# PIC32MXBOARD.net
KiCad netlist of a schematic drawn in EAGLE
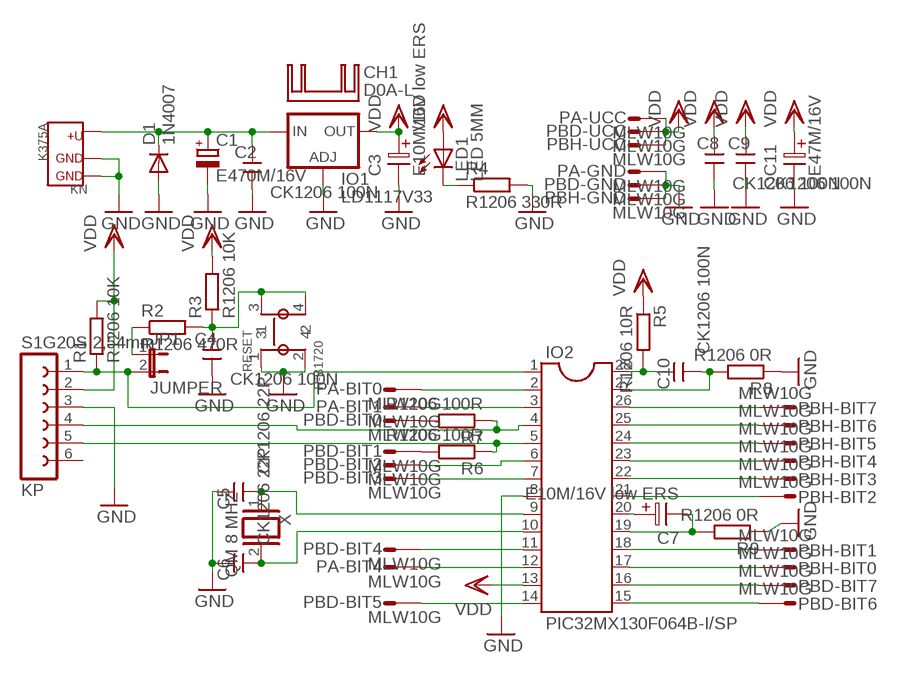
[diagram p0: schematic, sheet 1]

(export (version "E")
  (design (tool "Eeschema 10.0.6"))
  (components
    (comp (ref "C1")
      (value "E470M/16V")
      (footprint "eagle-import:E5-10,5")
      (libsource (lib "eagle-import") (part "CPOL-EUE5-10.5"))
    )
    (comp (ref "C2")
      (value "CK1206 100N")
      (footprint "eagle-import:CK+")
      (libsource (lib "eagle-import") (part "CK+"))
    )
    (comp (ref "C3")
      (value "E10M/16V low ERS")
      (footprint "eagle-import:ES-2,5L")
      (libsource (lib "eagle-import") (part "CEL2,5"))
    )
    (comp (ref "C4")
      (value "CK1206 100N")
      (footprint "eagle-import:CK+")
      (libsource (lib "eagle-import") (part "CK+"))
    )
    (comp (ref "C5")
      (value "CK1206 22P")
      (footprint "eagle-import:CK+")
      (libsource (lib "eagle-import") (part "CK+"))
    )
    (comp (ref "C6")
      (value "CK1206 22P")
      (footprint "eagle-import:CK+")
      (libsource (lib "eagle-import") (part "CK+"))
    )
    (comp (ref "C7")
      (value "E10M/16V low ERS")
      (footprint "eagle-import:ES-2,5L")
      (libsource (lib "eagle-import") (part "CEL2,5"))
    )
    (comp (ref "C8")
      (value "CK1206 100N")
      (footprint "eagle-import:CK+")
      (libsource (lib "eagle-import") (part "CK+"))
    )
    (comp (ref "C9")
      (value "CK1206 100N")
      (footprint "eagle-import:CK+")
      (libsource (lib "eagle-import") (part "CK+"))
    )
    (comp (ref "C10")
      (value "CK1206 100N")
      (footprint "eagle-import:CK+")
      (libsource (lib "eagle-import") (part "CK+"))
    )
    (comp (ref "C11")
      (value "E47M/16V")
      (footprint "eagle-import:ES-2,5L")
      (libsource (lib "eagle-import") (part "CEL2,5"))
    )
    (comp (ref "CH1")
      (value "D0A-L")
      (footprint "eagle-import:D02A-L")
      (libsource (lib "eagle-import") (part "D0A-L"))
    )
    (comp (ref "D1")
      (value "1N4007")
      (footprint "eagle-import:DO41-10")
      (libsource (lib "eagle-import") (part "1N4004"))
    )
    (comp (ref "IO1")
      (value "LD1117V33")
      (footprint "eagle-import:TO220L1")
      (libsource (lib "eagle-import") (part "LD117A?V33"))
    )
    (comp (ref "IO2")
      (value "PIC32MX130F064B-I/SP")
      (footprint "eagle-import:DIL28-3")
      (libsource (lib "eagle-import") (part "DIL28-3"))
    )
    (comp (ref "JP1")
      (value "JUMPER")
      (footprint "eagle-import:JP1")
      (libsource (lib "eagle-import") (part "JP1E"))
    )
    (comp (ref "KN")
      (value "K375A")
      (footprint "eagle-import:K375A")
      (libsource (lib "eagle-import") (part "K375A"))
    )
    (comp (ref "KP")
      (value "S1G20S 2,54mm")
      (footprint "eagle-import:FE06")
      (libsource (lib "eagle-import") (part "FE06-1"))
    )
    (comp (ref "LED1")
      (value "LED 5MM")
      (footprint "eagle-import:LED5MM")
      (libsource (lib "eagle-import") (part "LED5MM"))
    )
    (comp (ref "PA")
      (value "MLW10G")
      (footprint "eagle-import:MLW10G")
      (libsource (lib "eagle-import") (part "PSL10MLW10G"))
    )
    (comp (ref "PBD")
      (value "MLW10G")
      (footprint "eagle-import:MLW10G")
      (libsource (lib "eagle-import") (part "PSL10MLW10G"))
    )
    (comp (ref "PBH")
      (value "MLW10G")
      (footprint "eagle-import:MLW10G")
      (libsource (lib "eagle-import") (part "PSL10MLW10G"))
    )
    (comp (ref "R1")
      (value "R1206 10K")
      (footprint "eagle-import:R1206")
      (libsource (lib "eagle-import") (part "R-EU_R1206"))
    )
    (comp (ref "R2")
      (value "R1206 470R")
      (footprint "eagle-import:R1206")
      (libsource (lib "eagle-import") (part "R-EU_R1206"))
    )
    (comp (ref "R3")
      (value "R1206 10K")
      (footprint "eagle-import:R1206")
      (libsource (lib "eagle-import") (part "R-EU_R1206"))
    )
    (comp (ref "R4")
      (value "R1206 330R")
      (footprint "eagle-import:R1206")
      (libsource (lib "eagle-import") (part "R-EU_R1206"))
    )
    (comp (ref "R5")
      (value "R1206 10R")
      (footprint "eagle-import:R1206")
      (libsource (lib "eagle-import") (part "R-EU_R1206"))
    )
    (comp (ref "R6")
      (value "R1206 100R")
      (footprint "eagle-import:R1206")
      (libsource (lib "eagle-import") (part "R-EU_R1206"))
    )
    (comp (ref "R7")
      (value "R1206 100R")
      (footprint "eagle-import:R1206")
      (libsource (lib "eagle-import") (part "R-EU_R1206"))
    )
    (comp (ref "R8")
      (value "R1206 0R")
      (footprint "eagle-import:R1206")
      (libsource (lib "eagle-import") (part "R-EU_R1206"))
    )
    (comp (ref "R9")
      (value "R1206 0R")
      (footprint "eagle-import:R1206")
      (libsource (lib "eagle-import") (part "R-EU_R1206"))
    )
    (comp (ref "RESET")
      (value "P-B1720")
      (footprint "eagle-import:P-B1720")
      (libsource (lib "eagle-import") (part "P-B1720"))
    )
    (comp (ref "U$2")
      (value "RAM")
      (footprint "eagle-import:RAM")
      (libsource (lib "eagle-import") (part "RAM"))
    )
    (comp (ref "X")
      (value "QM 8 MHZ")
      (footprint "eagle-import:QS")
      (libsource (lib "eagle-import") (part "XTAL/S"))
    )
  )
  (nets
    (net (code "1") (name "GND") (class "Default")
      (node (ref "C1") (pin "-") (pinfunction "-_-") (pintype "passive"))
      (node (ref "C11") (pin "2") (pinfunction "2_2") (pintype "passive"))
      (node (ref "C2") (pin "2") (pinfunction "2_2") (pintype "passive"))
      (node (ref "C3") (pin "2") (pinfunction "2_2") (pintype "passive"))
      (node (ref "C4") (pin "2") (pinfunction "2_2") (pintype "passive"))
      (node (ref "C5") (pin "1") (pinfunction "1_1") (pintype "passive"))
      (node (ref "C6") (pin "1") (pinfunction "1_1") (pintype "passive"))
      (node (ref "C8") (pin "2") (pinfunction "2_2") (pintype "passive"))
      (node (ref "C9") (pin "2") (pinfunction "2_2") (pintype "passive"))
      (node (ref "D1") (pin "A") (pinfunction "A_A") (pintype "passive"))
      (node (ref "IO1") (pin "1") (pinfunction "ADJ_1") (pintype "input"))
      (node (ref "IO2") (pin "8") (pinfunction "8_8") (pintype "passive"))
      (node (ref "KN") (pin "1") (pinfunction "1_1") (pintype "bidirectional"))
      (node (ref "KN") (pin "3") (pinfunction "3_3") (pintype "bidirectional"))
      (node (ref "KP") (pin "3") (pinfunction "3_3") (pintype "passive"))
      (node (ref "PA") (pin "10") (pinfunction "S_10") (pintype "passive"))
      (node (ref "PBD") (pin "10") (pinfunction "S_10") (pintype "passive"))
      (node (ref "PBH") (pin "10") (pinfunction "S_10") (pintype "passive"))
      (node (ref "R4") (pin "2") (pinfunction "2_2") (pintype "passive"))
      (node (ref "R8") (pin "1") (pinfunction "1_1") (pintype "passive"))
      (node (ref "R9") (pin "1") (pinfunction "1_1") (pintype "passive"))
      (node (ref "RESET") (pin "1") (pinfunction "1_1") (pintype "bidirectional"))
      (node (ref "RESET") (pin "2") (pinfunction "2_2") (pintype "bidirectional"))
    )
    (net (code "2") (name "Net-(C4-Pad1)") (class "Default")
      (node (ref "C4") (pin "1") (pinfunction "1_1") (pintype "passive"))
      (node (ref "R2") (pin "2") (pinfunction "2_2") (pintype "passive"))
      (node (ref "R3") (pin "1") (pinfunction "1_1") (pintype "passive"))
      (node (ref "RESET") (pin "3") (pinfunction "3_3") (pintype "bidirectional"))
      (node (ref "RESET") (pin "4") (pinfunction "4_4") (pintype "bidirectional"))
    )
    (net (code "3") (name "Net-(C5-Pad2)") (class "Default")
      (node (ref "C5") (pin "2") (pinfunction "2_2") (pintype "passive"))
      (node (ref "IO2") (pin "9") (pinfunction "9_9") (pintype "passive"))
      (node (ref "X") (pin "1") (pinfunction "1_1") (pintype "passive"))
    )
    (net (code "4") (name "Net-(C6-Pad2)") (class "Default")
      (node (ref "C6") (pin "2") (pinfunction "2_2") (pintype "passive"))
      (node (ref "IO2") (pin "10") (pinfunction "10_10") (pintype "passive"))
      (node (ref "X") (pin "2") (pinfunction "2_2") (pintype "passive"))
    )
    (net (code "5") (name "Net-(C7-Pad1)") (class "Default")
      (node (ref "C7") (pin "1") (pinfunction "1_1") (pintype "passive"))
      (node (ref "IO2") (pin "20") (pinfunction "20_20") (pintype "passive"))
    )
    (net (code "6") (name "Net-(C7-Pad2)") (class "Default")
      (node (ref "C7") (pin "2") (pinfunction "2_2") (pintype "passive"))
      (node (ref "IO2") (pin "19") (pinfunction "19_19") (pintype "passive"))
      (node (ref "R9") (pin "2") (pinfunction "2_2") (pintype "passive"))
    )
    (net (code "7") (name "Net-(C10-Pad1)") (class "Default")
      (node (ref "C10") (pin "1") (pinfunction "1_1") (pintype "passive"))
      (node (ref "IO2") (pin "28") (pinfunction "28_28") (pintype "passive"))
      (node (ref "R5") (pin "2") (pinfunction "2_2") (pintype "passive"))
    )
    (net (code "8") (name "Net-(C10-Pad2)") (class "Default")
      (node (ref "C10") (pin "2") (pinfunction "2_2") (pintype "passive"))
      (node (ref "IO2") (pin "27") (pinfunction "27_27") (pintype "passive"))
      (node (ref "R8") (pin "2") (pinfunction "2_2") (pintype "passive"))
    )
    (net (code "9") (name "Net-(IO1-IN)") (class "Default")
      (node (ref "C1") (pin "+") (pinfunction "+_+") (pintype "passive"))
      (node (ref "C2") (pin "1") (pinfunction "1_1") (pintype "passive"))
      (node (ref "D1") (pin "C") (pinfunction "C_C") (pintype "passive"))
      (node (ref "IO1") (pin "3") (pinfunction "IN_3") (pintype "input"))
      (node (ref "KN") (pin "2") (pinfunction "2_2") (pintype "bidirectional"))
    )
    (net (code "10") (name "Net-(IO2-Pad1)") (class "Default")
      (node (ref "IO2") (pin "1") (pinfunction "1_1") (pintype "passive"))
      (node (ref "JP1") (pin "2") (pinfunction "2_2") (pintype "passive"))
      (node (ref "KP") (pin "1") (pinfunction "1_1") (pintype "passive"))
      (node (ref "R1") (pin "1") (pinfunction "1_1") (pintype "passive"))
    )
    (net (code "11") (name "Net-(IO2-Pad4)") (class "Default")
      (node (ref "IO2") (pin "4") (pinfunction "4_4") (pintype "passive"))
      (node (ref "KP") (pin "4") (pinfunction "4_4") (pintype "passive"))
      (node (ref "R7") (pin "1") (pinfunction "1_1") (pintype "passive"))
    )
    (net (code "12") (name "Net-(IO2-Pad5)") (class "Default")
      (node (ref "IO2") (pin "5") (pinfunction "5_5") (pintype "passive"))
      (node (ref "KP") (pin "5") (pinfunction "5_5") (pintype "passive"))
      (node (ref "R6") (pin "1") (pinfunction "1_1") (pintype "passive"))
    )
    (net (code "13") (name "Net-(JP1-Pad1)") (class "Default")
      (node (ref "JP1") (pin "1") (pinfunction "1_1") (pintype "passive"))
      (node (ref "R2") (pin "1") (pinfunction "1_1") (pintype "passive"))
    )
    (net (code "14") (name "Net-(LED1-C)") (class "Default")
      (node (ref "LED1") (pin "K") (pinfunction "C_K") (pintype "passive"))
      (node (ref "R4") (pin "1") (pinfunction "1_1") (pintype "passive"))
    )
    (net (code "15") (name "Net-(PAA-S)") (class "Default")
      (node (ref "IO2") (pin "2") (pinfunction "2_2") (pintype "passive"))
      (node (ref "PA") (pin "9") (pinfunction "S_9") (pintype "passive"))
    )
    (net (code "16") (name "Net-(PAB-S)") (class "Default")
      (node (ref "IO2") (pin "3") (pinfunction "3_3") (pintype "passive"))
      (node (ref "PA") (pin "8") (pinfunction "S_8") (pintype "passive"))
    )
    (net (code "17") (name "Net-(PAE-S)") (class "Default")
      (node (ref "IO2") (pin "12") (pinfunction "12_12") (pintype "passive"))
      (node (ref "PA") (pin "5") (pinfunction "S_5") (pintype "passive"))
    )
    (net (code "18") (name "Net-(PBDA-S)") (class "Default")
      (node (ref "PBD") (pin "9") (pinfunction "S_9") (pintype "passive"))
      (node (ref "R7") (pin "2") (pinfunction "2_2") (pintype "passive"))
    )
    (net (code "19") (name "Net-(PBDB-S)") (class "Default")
      (node (ref "PBD") (pin "8") (pinfunction "S_8") (pintype "passive"))
      (node (ref "R6") (pin "2") (pinfunction "2_2") (pintype "passive"))
    )
    (net (code "20") (name "Net-(PBDC-S)") (class "Default")
      (node (ref "IO2") (pin "6") (pinfunction "6_6") (pintype "passive"))
      (node (ref "PBD") (pin "7") (pinfunction "S_7") (pintype "passive"))
    )
    (net (code "21") (name "Net-(PBDD-S)") (class "Default")
      (node (ref "IO2") (pin "7") (pinfunction "7_7") (pintype "passive"))
      (node (ref "PBD") (pin "6") (pinfunction "S_6") (pintype "passive"))
    )
    (net (code "22") (name "Net-(PBDE-S)") (class "Default")
      (node (ref "IO2") (pin "11") (pinfunction "11_11") (pintype "passive"))
      (node (ref "PBD") (pin "5") (pinfunction "S_5") (pintype "passive"))
    )
    (net (code "23") (name "Net-(PBDF-S)") (class "Default")
      (node (ref "IO2") (pin "14") (pinfunction "14_14") (pintype "passive"))
      (node (ref "PBD") (pin "4") (pinfunction "S_4") (pintype "passive"))
    )
    (net (code "24") (name "Net-(PBDG-S)") (class "Default")
      (node (ref "IO2") (pin "15") (pinfunction "15_15") (pintype "passive"))
      (node (ref "PBD") (pin "3") (pinfunction "S_3") (pintype "passive"))
    )
    (net (code "25") (name "Net-(PBDH-S)") (class "Default")
      (node (ref "IO2") (pin "16") (pinfunction "16_16") (pintype "passive"))
      (node (ref "PBD") (pin "2") (pinfunction "S_2") (pintype "passive"))
    )
    (net (code "26") (name "Net-(PBHA-S)") (class "Default")
      (node (ref "IO2") (pin "17") (pinfunction "17_17") (pintype "passive"))
      (node (ref "PBH") (pin "9") (pinfunction "S_9") (pintype "passive"))
    )
    (net (code "27") (name "Net-(PBHB-S)") (class "Default")
      (node (ref "IO2") (pin "18") (pinfunction "18_18") (pintype "passive"))
      (node (ref "PBH") (pin "8") (pinfunction "S_8") (pintype "passive"))
    )
    (net (code "28") (name "Net-(PBHC-S)") (class "Default")
      (node (ref "IO2") (pin "21") (pinfunction "21_21") (pintype "passive"))
      (node (ref "PBH") (pin "7") (pinfunction "S_7") (pintype "passive"))
    )
    (net (code "29") (name "Net-(PBHD-S)") (class "Default")
      (node (ref "IO2") (pin "22") (pinfunction "22_22") (pintype "passive"))
      (node (ref "PBH") (pin "6") (pinfunction "S_6") (pintype "passive"))
    )
    (net (code "30") (name "Net-(PBHE-S)") (class "Default")
      (node (ref "IO2") (pin "23") (pinfunction "23_23") (pintype "passive"))
      (node (ref "PBH") (pin "5") (pinfunction "S_5") (pintype "passive"))
    )
    (net (code "31") (name "Net-(PBHF-S)") (class "Default")
      (node (ref "IO2") (pin "24") (pinfunction "24_24") (pintype "passive"))
      (node (ref "PBH") (pin "4") (pinfunction "S_4") (pintype "passive"))
    )
    (net (code "32") (name "Net-(PBHG-S)") (class "Default")
      (node (ref "IO2") (pin "25") (pinfunction "25_25") (pintype "passive"))
      (node (ref "PBH") (pin "3") (pinfunction "S_3") (pintype "passive"))
    )
    (net (code "33") (name "Net-(PBHH-S)") (class "Default")
      (node (ref "IO2") (pin "26") (pinfunction "26_26") (pintype "passive"))
      (node (ref "PBH") (pin "2") (pinfunction "S_2") (pintype "passive"))
    )
    (net (code "34") (name "VDD") (class "Default")
      (node (ref "C11") (pin "1") (pinfunction "1_1") (pintype "passive"))
      (node (ref "C3") (pin "1") (pinfunction "1_1") (pintype "passive"))
      (node (ref "C8") (pin "1") (pinfunction "1_1") (pintype "passive"))
      (node (ref "C9") (pin "1") (pinfunction "1_1") (pintype "passive"))
      (node (ref "IO1") (pin "2") (pinfunction "OUT_2") (pintype "passive"))
      (node (ref "IO2") (pin "13") (pinfunction "13_13") (pintype "passive"))
      (node (ref "KP") (pin "2") (pinfunction "2_2") (pintype "passive"))
      (node (ref "LED1") (pin "A") (pinfunction "A_A") (pintype "passive"))
      (node (ref "PA") (pin "1") (pinfunction "S_1") (pintype "passive"))
      (node (ref "PBD") (pin "1") (pinfunction "S_1") (pintype "passive"))
      (node (ref "PBH") (pin "1") (pinfunction "S_1") (pintype "passive"))
      (node (ref "R1") (pin "2") (pinfunction "2_2") (pintype "passive"))
      (node (ref "R3") (pin "2") (pinfunction "2_2") (pintype "passive"))
      (node (ref "R5") (pin "1") (pinfunction "1_1") (pintype "passive"))
    )
    (net (code "35") (name "unconnected-(KP-Pad6)") (class "Default")
      (node (ref "KP") (pin "6") (pinfunction "6_6") (pintype "passive"))
    )
  )
)
